# Connectors.net
KiCad netlist of a schematic drawn in Altium Designer
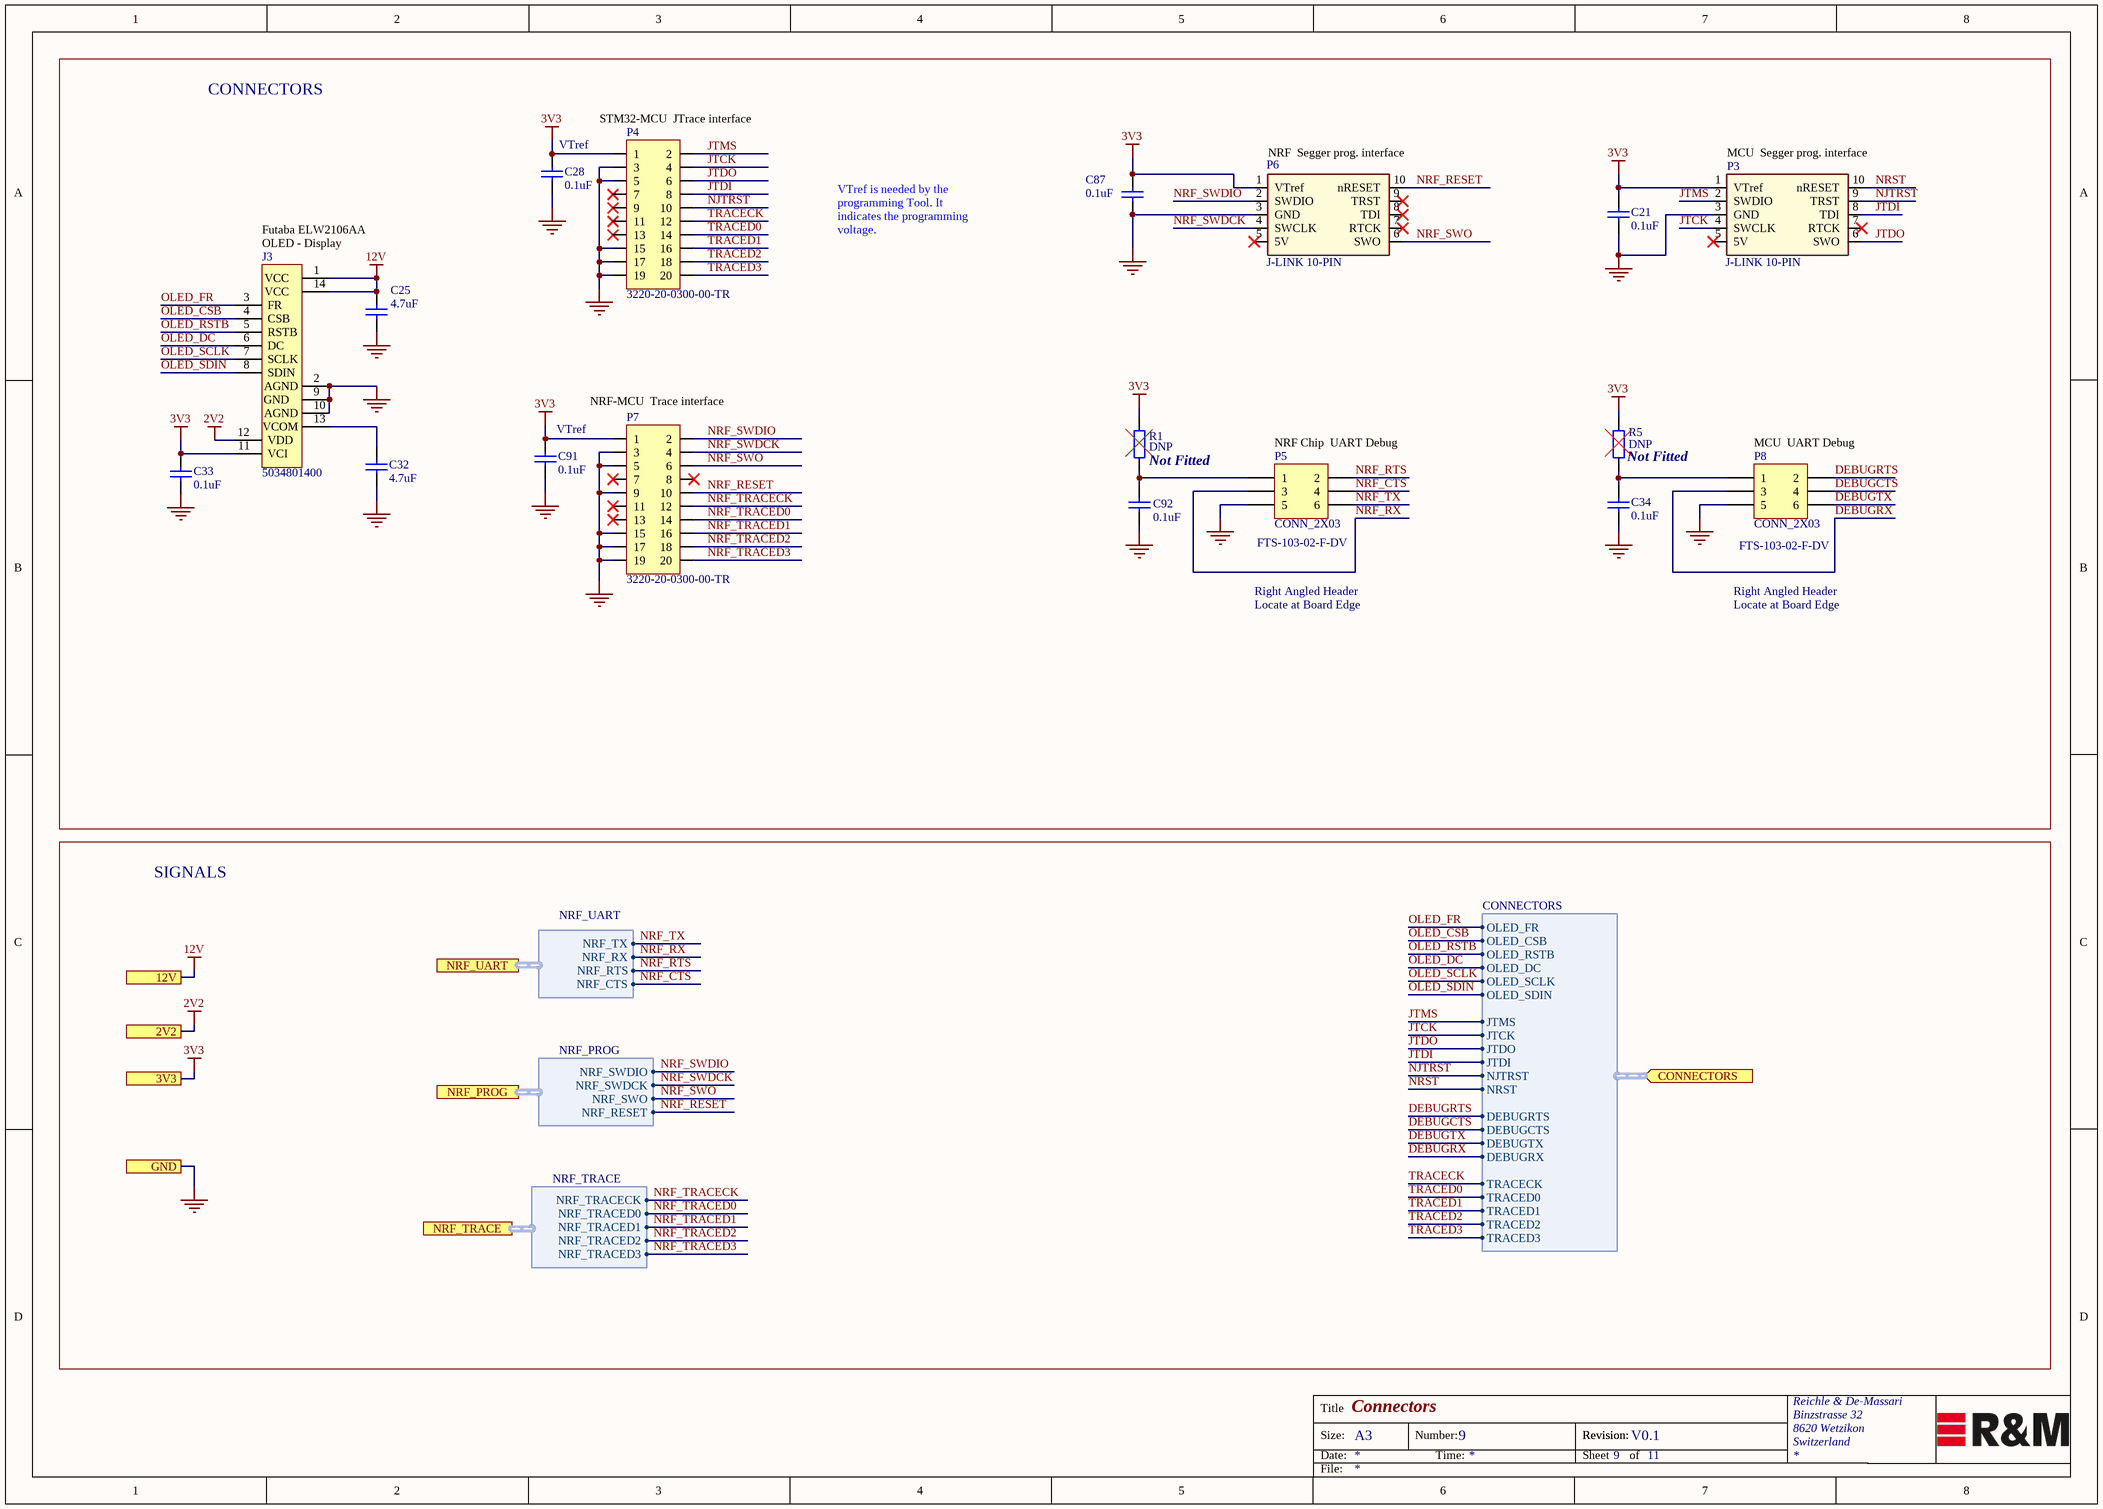
[diagram p0: Connectors.SchDoc]

(export (version "E")
  (design (tool "Eeschema 10.0.6"))
  (components
    (comp (ref "C21")
      (value "0.1uF")
      (footprint "Ceramic Capacitor 0402 EIA")
      (description "0.1µF ±20% 10V Ceramic Capacitor X5R 0402 (1005 Metric)")
      (fields (field (name "TOLERANCE") "20%") (field (name "VOLTAGE") "10VDC"))
      (libsource (lib "RDM_ALT_SCH") (part "Cap_0.1uF_0402_10V"))
    )
    (comp (ref "C25")
      (value "4.7uF")
      (footprint "Ceramic Capacitor 0603 EIA")
      (description "4.7µF ±10% 16V Ceramic Capacitor X5R 0603 (1608 Metric)")
      (fields (field (name "TOLERANCE") "10%") (field (name "VOLTAGE") "16 VDC"))
      (libsource (lib "RDM_ALT_SCH") (part "Cap_4.7uF_0603_16V"))
    )
    (comp (ref "C28")
      (value "0.1uF")
      (footprint "Ceramic Capacitor 0402 EIA")
      (description "0.1µF ±20% 10V Ceramic Capacitor X5R 0402 (1005 Metric)")
      (fields (field (name "TOLERANCE") "20%") (field (name "VOLTAGE") "10VDC"))
      (libsource (lib "RDM_ALT_SCH") (part "Cap_0.1uF_0402_10V"))
    )
    (comp (ref "C32")
      (value "4.7uF")
      (footprint "Ceramic Capacitor 0603 EIA")
      (description "4.7µF ±10% 16V Ceramic Capacitor X5R 0603 (1608 Metric)")
      (fields (field (name "TOLERANCE") "10%") (field (name "VOLTAGE") "16 VDC"))
      (libsource (lib "RDM_ALT_SCH") (part "Cap_4.7uF_0603_16V"))
    )
    (comp (ref "C33")
      (value "0.1uF")
      (footprint "Ceramic Capacitor 0402 EIA")
      (description "0.1µF ±20% 16V Ceramic Capacitor X7R 0402 (1005 Metric)")
      (fields (field (name "TOLERANCE") "20%") (field (name "VOLTAGE") "16VDC"))
      (libsource (lib "RDM_ALT_SCH") (part "Cap_0.1uF_0402_16V"))
    )
    (comp (ref "C34")
      (value "0.1uF")
      (footprint "Ceramic Capacitor 0402 EIA")
      (description "0.1µF ±20% 10V Ceramic Capacitor X5R 0402 (1005 Metric)")
      (fields (field (name "TOLERANCE") "20%") (field (name "VOLTAGE") "10VDC"))
      (libsource (lib "RDM_ALT_SCH") (part "Cap_0.1uF_0402_10V"))
    )
    (comp (ref "C87")
      (value "0.1uF")
      (footprint "Ceramic Capacitor 0402 EIA")
      (description "0.1µF ±20% 10V Ceramic Capacitor X5R 0402 (1005 Metric)")
      (fields (field (name "TOLERANCE") "20%") (field (name "VOLTAGE") "10VDC"))
      (libsource (lib "RDM_ALT_SCH") (part "Cap_0.1uF_0402_10V"))
    )
    (comp (ref "C91")
      (value "0.1uF")
      (footprint "Ceramic Capacitor 0402 EIA")
      (description "0.1µF ±20% 10V Ceramic Capacitor X5R 0402 (1005 Metric)")
      (fields (field (name "TOLERANCE") "20%") (field (name "VOLTAGE") "10VDC"))
      (libsource (lib "RDM_ALT_SCH") (part "Cap_0.1uF_0402_10V"))
    )
    (comp (ref "C92")
      (value "0.1uF")
      (footprint "Ceramic Capacitor 0402 EIA")
      (description "0.1µF ±20% 10V Ceramic Capacitor X5R 0402 (1005 Metric)")
      (fields (field (name "TOLERANCE") "20%") (field (name "VOLTAGE") "10VDC"))
      (libsource (lib "RDM_ALT_SCH") (part "Cap_0.1uF_0402_10V"))
    )
    (comp (ref "J3")
      (value "5034801400")
      (footprint "Molex_5034801400")
      (fields (field (name "MANUFACTURER") "Molex") (field (name "VOLTAGE") "50V"))
      (libsource (lib "RDM_ALT_SCH") (part "CONN_Molex_FPC_14pin_0.5mm"))
    )
    (comp (ref "P3")
      (value "J-LINK 10-PIN")
      (footprint "CONN-SEGGER-10-PIN")
      (description "Segger, J-Link 10-pin Needle Adapter")
      (libsource (lib "RDM_ALT_SCH") (part "CONN_Segger_10_PIN"))
    )
    (comp (ref "P4")
      (value "3220-20-0300-00-TR")
      (footprint "CNC_Tech_Conn_Header_2x10")
      (description "Connector Header Surface Mount 20 position 0.050\" (1.27mm)")
      (fields (field (name "MANUFACTURER") "CNC Tech"))
      (libsource (lib "RDM_ALT_SCH") (part "CONN_2X10_Header_1.27"))
    )
    (comp (ref "P5")
      (value "CONN_2X03")
      (footprint "Samtec_FTS-103-02-F-DV_6_R")
      (description "6Pin, 2Rows, MICRO LOW-PROFILE TERMINAL STRIPS")
      (fields (field (name "MANUFACTURER") "Samtec") (field (name "MANUFACTURER PARTNR") "FTS-103-02-F-DV"))
      (libsource (lib "RDM_ALT_SCH") (part "CONN_2X03_FTS-103-02-F-DV"))
    )
    (comp (ref "P6")
      (value "J-LINK 10-PIN")
      (footprint "CONN-SEGGER-10-PIN")
      (description "Segger, J-Link 10-pin Needle Adapter")
      (libsource (lib "RDM_ALT_SCH") (part "CONN_Segger_10_PIN"))
    )
    (comp (ref "P7")
      (value "3220-20-0300-00-TR")
      (footprint "CNC_Tech_Conn_Header_2x10")
      (description "Connector Header Surface Mount 20 position 0.050\" (1.27mm)")
      (fields (field (name "MANUFACTURER") "CNC Tech"))
      (libsource (lib "RDM_ALT_SCH") (part "CONN_2X10_Header_1.27"))
    )
    (comp (ref "P8")
      (value "CONN_2X03")
      (footprint "Samtec_FTS-103-02-F-DV_6_R")
      (description "6Pin, 2Rows, MICRO LOW-PROFILE TERMINAL STRIPS")
      (fields (field (name "MANUFACTURER") "Samtec") (field (name "MANUFACTURER PARTNR") "FTS-103-02-F-DV"))
      (libsource (lib "RDM_ALT_SCH") (part "CONN_2X03_FTS-103-02-F-DV"))
    )
    (comp (ref "R1")
      (value "DNP")
      (footprint "Resistor 0603 EIA")
      (description "Resistor: do not populate")
      (fields (field (name "MANUFACTURER") "do not populate"))
      (libsource (lib "RDM_ALT_SCH") (part "Res_DNP_0603"))
    )
    (comp (ref "R5")
      (value "DNP")
      (footprint "Resistor 0603 EIA")
      (description "Resistor: do not populate")
      (fields (field (name "MANUFACTURER") "do not populate"))
      (libsource (lib "RDM_ALT_SCH") (part "Res_DNP_0603"))
    )
  )
  (nets
    (net (code "5") (name "/DEBUGCTS") (class "Default")
      (node (ref "P8") (pin "4") (pinfunction "4_4") (pintype "passive"))
    )
    (net (code "6") (name "/DEBUGRTS") (class "Default")
      (node (ref "P8") (pin "2") (pinfunction "2_2") (pintype "passive"))
    )
    (net (code "7") (name "/DEBUGRX") (class "Default")
      (node (ref "P8") (pin "3") (pinfunction "3_3") (pintype "passive"))
    )
    (net (code "8") (name "/DEBUGTX") (class "Default")
      (node (ref "P8") (pin "6") (pinfunction "6_6") (pintype "passive"))
    )
    (net (code "9") (name "/JTCK") (class "Default")
      (node (ref "P3") (pin "4") (pinfunction "SWCLK_4") (pintype "passive"))
      (node (ref "P4") (pin "4") (pinfunction "4_4") (pintype "passive"))
    )
    (net (code "10") (name "/JTDI") (class "Default")
      (node (ref "P3") (pin "8") (pinfunction "TDI_8") (pintype "passive"))
      (node (ref "P4") (pin "8") (pinfunction "8_8") (pintype "passive"))
    )
    (net (code "11") (name "/JTDO") (class "Default")
      (node (ref "P3") (pin "6") (pinfunction "SWO_6") (pintype "passive"))
      (node (ref "P4") (pin "6") (pinfunction "6_6") (pintype "passive"))
    )
    (net (code "12") (name "/JTMS") (class "Default")
      (node (ref "P3") (pin "2") (pinfunction "SWDIO_2") (pintype "passive"))
      (node (ref "P4") (pin "2") (pinfunction "2_2") (pintype "passive"))
    )
    (net (code "13") (name "/NJTRST") (class "Default")
      (node (ref "P3") (pin "9") (pinfunction "TRST_9") (pintype "passive"))
      (node (ref "P4") (pin "10") (pinfunction "10_10") (pintype "passive"))
    )
    (net (code "14") (name "/NRF_CTS") (class "Default")
      (node (ref "P5") (pin "4") (pinfunction "4_4") (pintype "passive"))
    )
    (net (code "15") (name "/NRF_RESET") (class "Default")
      (node (ref "P6") (pin "10") (pinfunction "nRESET_10") (pintype "passive"))
      (node (ref "P7") (pin "10") (pinfunction "10_10") (pintype "passive"))
    )
    (net (code "16") (name "/NRF_RTS") (class "Default")
      (node (ref "P5") (pin "2") (pinfunction "2_2") (pintype "passive"))
    )
    (net (code "17") (name "/NRF_RX") (class "Default")
      (node (ref "P5") (pin "3") (pinfunction "3_3") (pintype "passive"))
    )
    (net (code "18") (name "/NRF_SWDCK") (class "Default")
      (node (ref "P6") (pin "4") (pinfunction "SWCLK_4") (pintype "passive"))
      (node (ref "P7") (pin "4") (pinfunction "4_4") (pintype "passive"))
    )
    (net (code "19") (name "/NRF_SWDIO") (class "Default")
      (node (ref "P6") (pin "2") (pinfunction "SWDIO_2") (pintype "passive"))
      (node (ref "P7") (pin "2") (pinfunction "2_2") (pintype "passive"))
    )
    (net (code "20") (name "/NRF_SWO") (class "Default")
      (node (ref "P6") (pin "6") (pinfunction "SWO_6") (pintype "passive"))
      (node (ref "P7") (pin "6") (pinfunction "6_6") (pintype "passive"))
    )
    (net (code "21") (name "/NRF_TRACECK") (class "Default")
      (node (ref "P7") (pin "12") (pinfunction "12_12") (pintype "passive"))
    )
    (net (code "22") (name "/NRF_TRACED0") (class "Default")
      (node (ref "P7") (pin "14") (pinfunction "14_14") (pintype "passive"))
    )
    (net (code "23") (name "/NRF_TRACED1") (class "Default")
      (node (ref "P7") (pin "16") (pinfunction "16_16") (pintype "passive"))
    )
    (net (code "24") (name "/NRF_TRACED2") (class "Default")
      (node (ref "P7") (pin "18") (pinfunction "18_18") (pintype "passive"))
    )
    (net (code "25") (name "/NRF_TRACED3") (class "Default")
      (node (ref "P7") (pin "20") (pinfunction "20_20") (pintype "passive"))
    )
    (net (code "26") (name "/NRF_TX") (class "Default")
      (node (ref "P5") (pin "6") (pinfunction "6_6") (pintype "passive"))
    )
    (net (code "27") (name "/NRST") (class "Default")
      (node (ref "P3") (pin "10") (pinfunction "nRESET_10") (pintype "passive"))
    )
    (net (code "28") (name "/OLED_CSB") (class "Default")
      (node (ref "J3") (pin "4") (pinfunction "CSB_4") (pintype "passive"))
    )
    (net (code "29") (name "/OLED_DC") (class "Default")
      (node (ref "J3") (pin "6") (pinfunction "DC_6") (pintype "passive"))
    )
    (net (code "30") (name "/OLED_FR") (class "Default")
      (node (ref "J3") (pin "3") (pinfunction "FR_3") (pintype "passive"))
    )
    (net (code "31") (name "/OLED_RSTB") (class "Default")
      (node (ref "J3") (pin "5") (pinfunction "RSTB_5") (pintype "passive"))
    )
    (net (code "32") (name "/OLED_SCLK") (class "Default")
      (node (ref "J3") (pin "7") (pinfunction "SCLK_7") (pintype "passive"))
    )
    (net (code "33") (name "/OLED_SDIN") (class "Default")
      (node (ref "J3") (pin "8") (pinfunction "SDIN_8") (pintype "passive"))
    )
    (net (code "34") (name "/TRACECK") (class "Default")
      (node (ref "P4") (pin "12") (pinfunction "12_12") (pintype "passive"))
    )
    (net (code "35") (name "/TRACED0") (class "Default")
      (node (ref "P4") (pin "14") (pinfunction "14_14") (pintype "passive"))
    )
    (net (code "36") (name "/TRACED1") (class "Default")
      (node (ref "P4") (pin "16") (pinfunction "16_16") (pintype "passive"))
    )
    (net (code "37") (name "/TRACED2") (class "Default")
      (node (ref "P4") (pin "18") (pinfunction "18_18") (pintype "passive"))
    )
    (net (code "38") (name "/TRACED3") (class "Default")
      (node (ref "P4") (pin "20") (pinfunction "20_20") (pintype "passive"))
    )
    (net (code "43") (name "2V2") (class "Default")
      (node (ref "J3") (pin "12") (pinfunction "VDD_12") (pintype "passive"))
    )
    (net (code "44") (name "3V3") (class "Default")
      (node (ref "C21") (pin "2") (pinfunction "2_2") (pintype "passive"))
      (node (ref "C28") (pin "2") (pinfunction "2_2") (pintype "passive"))
      (node (ref "C33") (pin "2") (pinfunction "2_2") (pintype "passive"))
      (node (ref "C87") (pin "2") (pinfunction "2_2") (pintype "passive"))
      (node (ref "C91") (pin "2") (pinfunction "2_2") (pintype "passive"))
      (node (ref "J3") (pin "11") (pinfunction "VCI_11") (pintype "passive"))
      (node (ref "P3") (pin "1") (pinfunction "VTref_1") (pintype "passive"))
      (node (ref "P4") (pin "1") (pinfunction "1_1") (pintype "passive"))
      (node (ref "P6") (pin "1") (pinfunction "VTref_1") (pintype "passive"))
      (node (ref "P7") (pin "1") (pinfunction "1_1") (pintype "passive"))
      (node (ref "R1") (pin "1") (pinfunction "1_1") (pintype "passive"))
      (node (ref "R5") (pin "1") (pinfunction "1_1") (pintype "passive"))
    )
    (net (code "45") (name "12V") (class "Default")
      (node (ref "C25") (pin "2") (pinfunction "2_2") (pintype "passive"))
      (node (ref "J3") (pin "1") (pinfunction "VCC_1") (pintype "passive"))
      (node (ref "J3") (pin "14") (pinfunction "VCC_14") (pintype "passive"))
    )
    (net (code "46") (name "GND") (class "Default")
      (node (ref "C21") (pin "1") (pinfunction "1_1") (pintype "passive"))
      (node (ref "C25") (pin "1") (pinfunction "1_1") (pintype "passive"))
      (node (ref "C28") (pin "1") (pinfunction "1_1") (pintype "passive"))
      (node (ref "C32") (pin "1") (pinfunction "1_1") (pintype "passive"))
      (node (ref "C33") (pin "1") (pinfunction "1_1") (pintype "passive"))
      (node (ref "C34") (pin "1") (pinfunction "1_1") (pintype "passive"))
      (node (ref "C87") (pin "1") (pinfunction "1_1") (pintype "passive"))
      (node (ref "C91") (pin "1") (pinfunction "1_1") (pintype "passive"))
      (node (ref "C92") (pin "1") (pinfunction "1_1") (pintype "passive"))
      (node (ref "J3") (pin "10") (pinfunction "AGND_10") (pintype "passive"))
      (node (ref "J3") (pin "2") (pinfunction "AGND_2") (pintype "passive"))
      (node (ref "J3") (pin "9") (pinfunction "GND_9") (pintype "passive"))
      (node (ref "P3") (pin "3") (pinfunction "GND_3") (pintype "passive"))
      (node (ref "P4") (pin "15") (pinfunction "15_15") (pintype "passive"))
      (node (ref "P4") (pin "17") (pinfunction "17_17") (pintype "passive"))
      (node (ref "P4") (pin "19") (pinfunction "19_19") (pintype "passive"))
      (node (ref "P4") (pin "3") (pinfunction "3_3") (pintype "passive"))
      (node (ref "P4") (pin "5") (pinfunction "5_5") (pintype "passive"))
      (node (ref "P5") (pin "5") (pinfunction "5_5") (pintype "passive"))
      (node (ref "P6") (pin "3") (pinfunction "GND_3") (pintype "passive"))
      (node (ref "P7") (pin "15") (pinfunction "15_15") (pintype "passive"))
      (node (ref "P7") (pin "17") (pinfunction "17_17") (pintype "passive"))
      (node (ref "P7") (pin "19") (pinfunction "19_19") (pintype "passive"))
      (node (ref "P7") (pin "3") (pinfunction "3_3") (pintype "passive"))
      (node (ref "P7") (pin "5") (pinfunction "5_5") (pintype "passive"))
      (node (ref "P7") (pin "9") (pinfunction "9_9") (pintype "passive"))
      (node (ref "P8") (pin "5") (pinfunction "5_5") (pintype "passive"))
    )
    (net (code "47") (name "Net-(C34-Pad2)") (class "Default")
      (node (ref "C34") (pin "2") (pinfunction "2_2") (pintype "passive"))
      (node (ref "P8") (pin "1") (pinfunction "1_1") (pintype "passive"))
      (node (ref "R5") (pin "2") (pinfunction "2_2") (pintype "passive"))
    )
    (net (code "48") (name "Net-(C92-Pad2)") (class "Default")
      (node (ref "C92") (pin "2") (pinfunction "2_2") (pintype "passive"))
      (node (ref "P5") (pin "1") (pinfunction "1_1") (pintype "passive"))
      (node (ref "R1") (pin "2") (pinfunction "2_2") (pintype "passive"))
    )
    (net (code "49") (name "Net-(J3-VCOM)") (class "Default")
      (node (ref "C32") (pin "2") (pinfunction "2_2") (pintype "passive"))
      (node (ref "J3") (pin "13") (pinfunction "VCOM_13") (pintype "passive"))
    )
    (net (code "50") (name "unconnected-(P3-5V-Pad5)") (class "Default")
      (node (ref "P3") (pin "5") (pinfunction "5V_5") (pintype "passive+no_connect"))
    )
    (net (code "51") (name "unconnected-(P3-RTCK-Pad7)") (class "Default")
      (node (ref "P3") (pin "7") (pinfunction "RTCK_7") (pintype "passive+no_connect"))
    )
    (net (code "52") (name "unconnected-(P4-Pad7)") (class "Default")
      (node (ref "P4") (pin "7") (pinfunction "7_7") (pintype "passive+no_connect"))
    )
    (net (code "53") (name "unconnected-(P4-Pad9)") (class "Default")
      (node (ref "P4") (pin "9") (pinfunction "9_9") (pintype "passive+no_connect"))
    )
    (net (code "54") (name "unconnected-(P4-Pad11)") (class "Default")
      (node (ref "P4") (pin "11") (pinfunction "11_11") (pintype "passive+no_connect"))
    )
    (net (code "55") (name "unconnected-(P4-Pad13)") (class "Default")
      (node (ref "P4") (pin "13") (pinfunction "13_13") (pintype "passive+no_connect"))
    )
    (net (code "56") (name "unconnected-(P6-5V-Pad5)") (class "Default")
      (node (ref "P6") (pin "5") (pinfunction "5V_5") (pintype "passive+no_connect"))
    )
    (net (code "57") (name "unconnected-(P6-RTCK-Pad7)") (class "Default")
      (node (ref "P6") (pin "7") (pinfunction "RTCK_7") (pintype "passive+no_connect"))
    )
    (net (code "58") (name "unconnected-(P6-TDI-Pad8)") (class "Default")
      (node (ref "P6") (pin "8") (pinfunction "TDI_8") (pintype "passive+no_connect"))
    )
    (net (code "59") (name "unconnected-(P6-TRST-Pad9)") (class "Default")
      (node (ref "P6") (pin "9") (pinfunction "TRST_9") (pintype "passive+no_connect"))
    )
    (net (code "60") (name "unconnected-(P7-Pad7)") (class "Default")
      (node (ref "P7") (pin "7") (pinfunction "7_7") (pintype "passive+no_connect"))
    )
    (net (code "61") (name "unconnected-(P7-Pad8)") (class "Default")
      (node (ref "P7") (pin "8") (pinfunction "8_8") (pintype "passive+no_connect"))
    )
    (net (code "62") (name "unconnected-(P7-Pad11)") (class "Default")
      (node (ref "P7") (pin "11") (pinfunction "11_11") (pintype "passive+no_connect"))
    )
    (net (code "63") (name "unconnected-(P7-Pad13)") (class "Default")
      (node (ref "P7") (pin "13") (pinfunction "13_13") (pintype "passive+no_connect"))
    )
  )
)
